# dcb_single_channel.net
KiCad netlist of a schematic drawn in Altium Designer
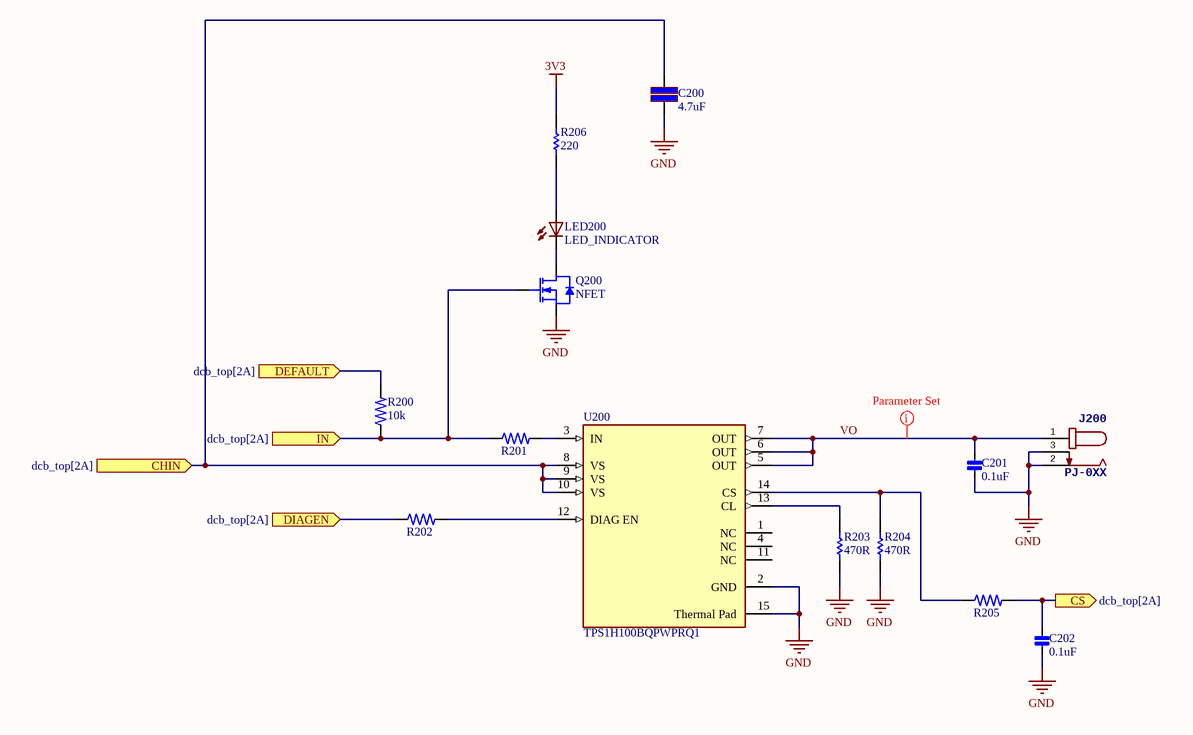
[diagram p0: dcb_single_channel.SchDoc]

(export (version "E")
  (design (tool "Eeschema 10.0.6"))
  (components
    (comp (ref "C200")
      (value "4.7uF")
      (footprint "CAPC3225X20N")
      (description "CAP CER 4.7UF 50V X7R 1210")
      (fields (field (name "VOLTAGE") "50V") (field (name "TOLERANCE") "10%"))
      (libsource (lib "StackFoundry LLC") (part "4.7uF"))
    )
    (comp (ref "C201")
      (value "0.1uF")
      (footprint "FP-CL10-IPC_B")
      (description "Cap Ceramic 0.1uF 50V X7R 20% SMD 0603 125C Paper T/R")
      (fields (field (name "VOLTAGE") "50V") (field (name "Comment") "CAP 0.1uF 50V X7R 0603"))
      (libsource (lib "StackFoundry LLC") (part "C-EU"))
    )
    (comp (ref "C202")
      (value "0.1uF")
      (footprint "FP-CL10-IPC_B")
      (description "Cap Ceramic 0.1uF 50V X7R 20% SMD 0603 125C Paper T/R")
      (fields (field (name "VOLTAGE") "50V") (field (name "Comment") "CAP 0.1uF 50V X7R 0603"))
      (libsource (lib "StackFoundry LLC") (part "C-EU"))
    )
    (comp (ref "J200")
      (value "PJ-0XX")
      (footprint "CUI-PJ-002A_V")
      (description "2.0 x 6.5 mm, 2.5 A, Horizontal, Through Hole, Dc Power Jack Connector")
      (libsource (lib "StackFoundry LLC") (part "Symbol"))
    )
    (comp (ref "LED200")
      (value "LED_INDICATOR")
      (footprint "LED5MM")
      (libsource (lib "StackFoundry LLC") (part "LED_INDICATOR"))
    )
    (comp (ref "Q200")
      (value "NFET")
      (footprint "SOT23-3")
      (libsource (lib "StackFoundry LLC") (part "NFET"))
    )
    (comp (ref "R200")
      (value "10k")
      (footprint "RESC1608-IPC-ML")
      (description "Res General Purpose Thick Film 0603 10K Ohm 1% 1/10W ±100ppm/°C Molded SMD Paper T/R")
      (fields (field (name "Comment") "10K 0603 1%"))
      (libsource (lib "StackFoundry LLC") (part "R-US"))
    )
    (comp (ref "R201")
      (value "4.7k 0603 1%")
      (footprint "RESC1608-IPC-ML")
      (description "RES SMD 4.7K OHM 1% 1/10W 0603")
      (libsource (lib "StackFoundry LLC") (part "R-US"))
    )
    (comp (ref "R202")
      (value "4.7k 0603 1%")
      (footprint "RESC1608-IPC-ML")
      (description "RES SMD 4.7K OHM 1% 1/10W 0603")
      (libsource (lib "StackFoundry LLC") (part "R-US"))
    )
    (comp (ref "R203")
      (value "470R")
      (footprint "RESC2013X60X35LL10T20")
      (description "SMD Chip Resistor, 470 Ohm, ± 1%, 125 mW, 0805 [2012 Metric], Thick Film, General Purpose")
      (fields (field (name "TOLERANCE") "1%") (field (name "Comment") "RC0805FR-07470RL"))
      (libsource (lib "StackFoundry LLC") (part "RES-2"))
    )
    (comp (ref "R204")
      (value "470R")
      (footprint "RESC2013X60X35LL10T20")
      (description "SMD Chip Resistor, 470 Ohm, ± 1%, 125 mW, 0805 [2012 Metric], Thick Film, General Purpose")
      (fields (field (name "TOLERANCE") "1%") (field (name "Comment") "RC0805FR-07470RL"))
      (libsource (lib "StackFoundry LLC") (part "RES-2"))
    )
    (comp (ref "R205")
      (value "4.7k 0603 1%")
      (footprint "RESC1608-IPC-ML")
      (description "RES SMD 4.7K OHM 1% 1/10W 0603")
      (libsource (lib "StackFoundry LLC") (part "R-US"))
    )
    (comp (ref "R206")
      (value "220")
      (footprint "RESC1608-IPC-ML")
      (fields (field (name "TOLERANCE") "5%") (field (name "Comment") "220R 0603 5%"))
      (libsource (lib "StackFoundry LLC") (part "RES-2"))
    )
    (comp (ref "U200")
      (value "TPS1H100BQPWPRQ1")
      (footprint "FP-PWP0014C-IPC_C")
      (description "Current Limit SW 1-IN 1-OUT 5V to 40V 4A Automotive 14-Pin HTSSOP EP T/R")
      (libsource (lib "StackFoundry LLC") (part "9438d576f614b53ae075b99ddcc45f2"))
    )
  )
  (nets
    (net (code "1") (name "/CHIN") (class "Default")
      (node (ref "C200") (pin "2") (pintype "passive"))
      (node (ref "U200") (pin "10") (pinfunction "VS_10") (pintype "input"))
      (node (ref "U200") (pin "8") (pinfunction "VS_8") (pintype "input"))
      (node (ref "U200") (pin "9") (pinfunction "VS_9") (pintype "input"))
    )
    (net (code "2") (name "/CS") (class "Default")
      (node (ref "C202") (pin "1") (pinfunction "1_1") (pintype "passive"))
      (node (ref "R205") (pin "2") (pinfunction "2_2") (pintype "passive"))
    )
    (net (code "3") (name "/DEFAULT") (class "Default")
      (node (ref "R200") (pin "2") (pinfunction "2_2") (pintype "passive"))
    )
    (net (code "4") (name "/DIAGEN") (class "Default")
      (node (ref "R202") (pin "1") (pinfunction "1_1") (pintype "passive"))
    )
    (net (code "5") (name "/IN") (class "Default")
      (node (ref "Q200") (pin "1") (pinfunction "G_1") (pintype "passive"))
      (node (ref "R200") (pin "1") (pinfunction "1_1") (pintype "passive"))
      (node (ref "R201") (pin "1") (pinfunction "1_1") (pintype "passive"))
    )
    (net (code "6") (name "/VO") (class "Default")
      (node (ref "C201") (pin "1") (pinfunction "1_1") (pintype "passive"))
      (node (ref "J200") (pin "1") (pinfunction "1_1") (pintype "passive"))
      (node (ref "U200") (pin "5") (pinfunction "OUT_5") (pintype "output"))
      (node (ref "U200") (pin "6") (pinfunction "OUT_6") (pintype "output"))
      (node (ref "U200") (pin "7") (pinfunction "OUT_7") (pintype "output"))
    )
    (net (code "7") (name "3V3") (class "Default")
      (node (ref "R206") (pin "2") (pinfunction "2_2") (pintype "passive"))
    )
    (net (code "8") (name "GND") (class "Default")
      (node (ref "C200") (pin "1") (pintype "passive"))
      (node (ref "C201") (pin "2") (pinfunction "2_2") (pintype "passive"))
      (node (ref "C202") (pin "2") (pinfunction "2_2") (pintype "passive"))
      (node (ref "J200") (pin "2") (pinfunction "2_2") (pintype "passive"))
      (node (ref "J200") (pin "3") (pinfunction "3_3") (pintype "passive"))
      (node (ref "Q200") (pin "2") (pinfunction "S_2") (pintype "passive"))
      (node (ref "R203") (pin "1") (pinfunction "1_1") (pintype "passive"))
      (node (ref "R204") (pin "1") (pinfunction "1_1") (pintype "passive"))
      (node (ref "U200") (pin "15") (pinfunction "Thermal_Pad_15") (pintype "passive"))
      (node (ref "U200") (pin "2") (pinfunction "GND_2") (pintype "power_in"))
    )
    (net (code "9") (name "Net-(LED200-PadA)") (class "Default")
      (node (ref "LED200") (pin "A") (pinfunction "A_A") (pintype "passive"))
      (node (ref "R206") (pin "1") (pinfunction "1_1") (pintype "passive"))
    )
    (net (code "10") (name "Net-(Q200-D)") (class "Default")
      (node (ref "LED200") (pin "C") (pinfunction "C_C") (pintype "passive"))
      (node (ref "Q200") (pin "3") (pinfunction "D_3") (pintype "passive"))
    )
    (net (code "11") (name "Net-(U200-CL)") (class "Default")
      (node (ref "R203") (pin "2") (pinfunction "2_2") (pintype "passive"))
      (node (ref "U200") (pin "13") (pinfunction "CL_13") (pintype "output"))
    )
    (net (code "12") (name "Net-(U200-CS)") (class "Default")
      (node (ref "R204") (pin "2") (pinfunction "2_2") (pintype "passive"))
      (node (ref "R205") (pin "1") (pinfunction "1_1") (pintype "passive"))
      (node (ref "U200") (pin "14") (pinfunction "CS_14") (pintype "output"))
    )
    (net (code "13") (name "Net-(U200-DIAG_EN)") (class "Default")
      (node (ref "R202") (pin "2") (pinfunction "2_2") (pintype "passive"))
      (node (ref "U200") (pin "12") (pinfunction "DIAG_EN_12") (pintype "input"))
    )
    (net (code "14") (name "Net-(U200-IN)") (class "Default")
      (node (ref "R201") (pin "2") (pinfunction "2_2") (pintype "passive"))
      (node (ref "U200") (pin "3") (pinfunction "IN_3") (pintype "input"))
    )
    (net (code "15") (name "unconnected-(U200-NC-Pad1)") (class "Default")
      (node (ref "U200") (pin "1") (pinfunction "NC_1") (pintype "passive"))
    )
    (net (code "16") (name "unconnected-(U200-NC-Pad4)") (class "Default")
      (node (ref "U200") (pin "4") (pinfunction "NC_4") (pintype "passive"))
    )
    (net (code "17") (name "unconnected-(U200-NC-Pad11)") (class "Default")
      (node (ref "U200") (pin "11") (pinfunction "NC_11") (pintype "passive"))
    )
  )
)
